# Vorsignal_Wiederholer.net
KiCad netlist of a schematic drawn in EAGLE
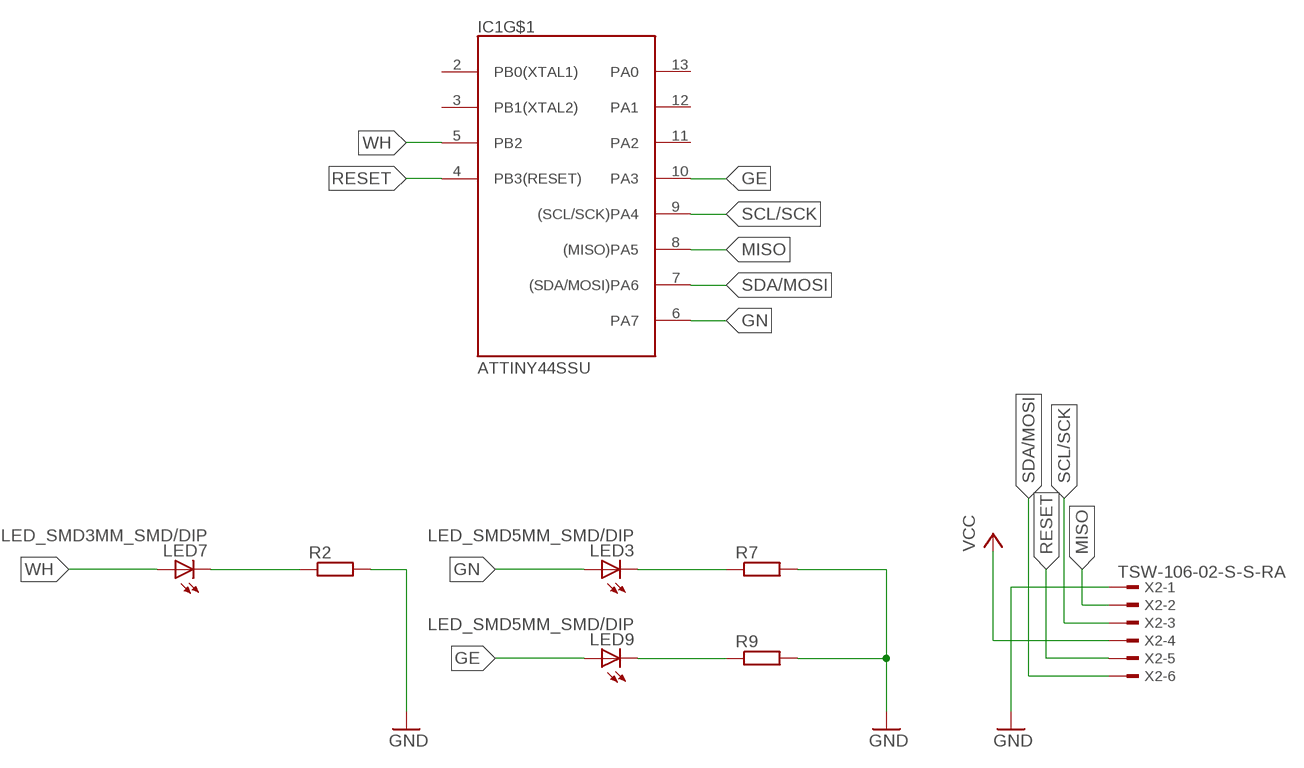
[diagram p0: schematic, sheet 1]

(export (version "E")
  (design (tool "Eeschema 10.0.6"))
  (components
    (comp (ref "IC1")
      (value "ATTINY44SSU")
      (footprint "eagle-import:SO14")
      (libsource (lib "eagle-import") (part "ATTINY44SSU"))
    )
    (comp (ref "LED3")
      (value "LED_SMD5MM_SMD/DIP")
      (footprint "eagle-import:5MM_FLAT_DIP_SMDLED")
      (libsource (lib "eagle-import") (part "LED_SMD5MM_SMD/DIP"))
    )
    (comp (ref "LED7")
      (value "LED_SMD3MM_SMD/DIP")
      (footprint "eagle-import:3MM_FLAT_DIP_SMDLED")
      (libsource (lib "eagle-import") (part "LED_SMD3MM_SMD/DIP"))
    )
    (comp (ref "LED9")
      (value "LED_SMD5MM_SMD/DIP")
      (footprint "eagle-import:5MM_FLAT_DIP_SMDLED")
      (libsource (lib "eagle-import") (part "LED_SMD5MM_SMD/DIP"))
    )
    (comp (ref "R2")
      (value "R-EU_R0603")
      (footprint "eagle-import:R0603")
      (libsource (lib "eagle-import") (part "R-EU_R0603"))
    )
    (comp (ref "R7")
      (value "R-EU_R0603")
      (footprint "eagle-import:R0603")
      (libsource (lib "eagle-import") (part "R-EU_R0603"))
    )
    (comp (ref "R9")
      (value "R-EU_R0603")
      (footprint "eagle-import:R0603")
      (libsource (lib "eagle-import") (part "R-EU_R0603"))
    )
    (comp (ref "X2")
      (value "TSW-106-02-S-S-RA")
      (footprint "eagle-import:TSW-106-02-S-S-RA")
      (libsource (lib "eagle-import") (part "TSW-106-02-S-S-RA"))
    )
  )
  (nets
    (net (code "1") (name "GE") (class "Default")
      (node (ref "IC1") (pin "10") (pinfunction "PA3_10") (pintype "bidirectional"))
      (node (ref "LED9") (pin "+") (pinfunction "A_+") (pintype "passive"))
    )
    (net (code "2") (name "GN") (class "Default")
      (node (ref "IC1") (pin "6") (pinfunction "PA7_6") (pintype "bidirectional"))
      (node (ref "LED3") (pin "+") (pinfunction "A_+") (pintype "passive"))
    )
    (net (code "3") (name "GND") (class "Default")
      (node (ref "R2") (pin "2") (pinfunction "2_2") (pintype "passive"))
      (node (ref "R7") (pin "2") (pinfunction "2_2") (pintype "passive"))
      (node (ref "R9") (pin "2") (pinfunction "2_2") (pintype "passive"))
      (node (ref "X2") (pin "1") (pinfunction "1_1") (pintype "passive"))
    )
    (net (code "4") (name "MISO") (class "Default")
      (node (ref "IC1") (pin "8") (pinfunction "(MISO)PA5_8") (pintype "bidirectional"))
      (node (ref "X2") (pin "2") (pinfunction "1_2") (pintype "passive"))
    )
    (net (code "5") (name "Net-(LED3-C)") (class "Default")
      (node (ref "LED3") (pin "-") (pinfunction "C_-") (pintype "passive"))
      (node (ref "R7") (pin "1") (pinfunction "1_1") (pintype "passive"))
    )
    (net (code "6") (name "Net-(LED7-C)") (class "Default")
      (node (ref "LED7") (pin "-") (pinfunction "C_-") (pintype "passive"))
      (node (ref "R2") (pin "1") (pinfunction "1_1") (pintype "passive"))
    )
    (net (code "7") (name "Net-(LED9-C)") (class "Default")
      (node (ref "LED9") (pin "-") (pinfunction "C_-") (pintype "passive"))
      (node (ref "R9") (pin "1") (pinfunction "1_1") (pintype "passive"))
    )
    (net (code "8") (name "RESET") (class "Default")
      (node (ref "IC1") (pin "4") (pinfunction "PB3(RESET)_4") (pintype "bidirectional"))
      (node (ref "X2") (pin "5") (pinfunction "1_5") (pintype "passive"))
    )
    (net (code "9") (name "SCL{slash}SCK") (class "Default")
      (node (ref "IC1") (pin "9") (pinfunction "(SCL/SCK)PA4_9") (pintype "bidirectional"))
      (node (ref "X2") (pin "3") (pinfunction "1_3") (pintype "passive"))
    )
    (net (code "10") (name "SDA{slash}MOSI") (class "Default")
      (node (ref "IC1") (pin "7") (pinfunction "(SDA/MOSI)PA6_7") (pintype "bidirectional"))
      (node (ref "X2") (pin "6") (pinfunction "1_6") (pintype "passive"))
    )
    (net (code "11") (name "VCC") (class "Default")
      (node (ref "X2") (pin "4") (pinfunction "1_4") (pintype "passive"))
    )
    (net (code "12") (name "WH") (class "Default")
      (node (ref "IC1") (pin "5") (pinfunction "PB2_5") (pintype "bidirectional"))
      (node (ref "LED7") (pin "+") (pinfunction "A_+") (pintype "passive"))
    )
    (net (code "13") (name "unconnected-(IC1A-PA0-Pad13)") (class "Default")
      (node (ref "IC1") (pin "13") (pinfunction "PA0_13") (pintype "bidirectional"))
    )
    (net (code "14") (name "unconnected-(IC1A-PA1-Pad12)") (class "Default")
      (node (ref "IC1") (pin "12") (pinfunction "PA1_12") (pintype "bidirectional"))
    )
    (net (code "15") (name "unconnected-(IC1A-PA2-Pad11)") (class "Default")
      (node (ref "IC1") (pin "11") (pinfunction "PA2_11") (pintype "bidirectional"))
    )
    (net (code "16") (name "unconnected-(IC1A-PB0(XTAL1)-Pad2)") (class "Default")
      (node (ref "IC1") (pin "2") (pinfunction "PB0(XTAL1)_2") (pintype "bidirectional"))
    )
    (net (code "17") (name "unconnected-(IC1A-PB1(XTAL2)-Pad3)") (class "Default")
      (node (ref "IC1") (pin "3") (pinfunction "PB1(XTAL2)_3") (pintype "bidirectional"))
    )
  )
)
